# RFID_RC632.net
KiCad netlist of a schematic drawn in Altium Designer
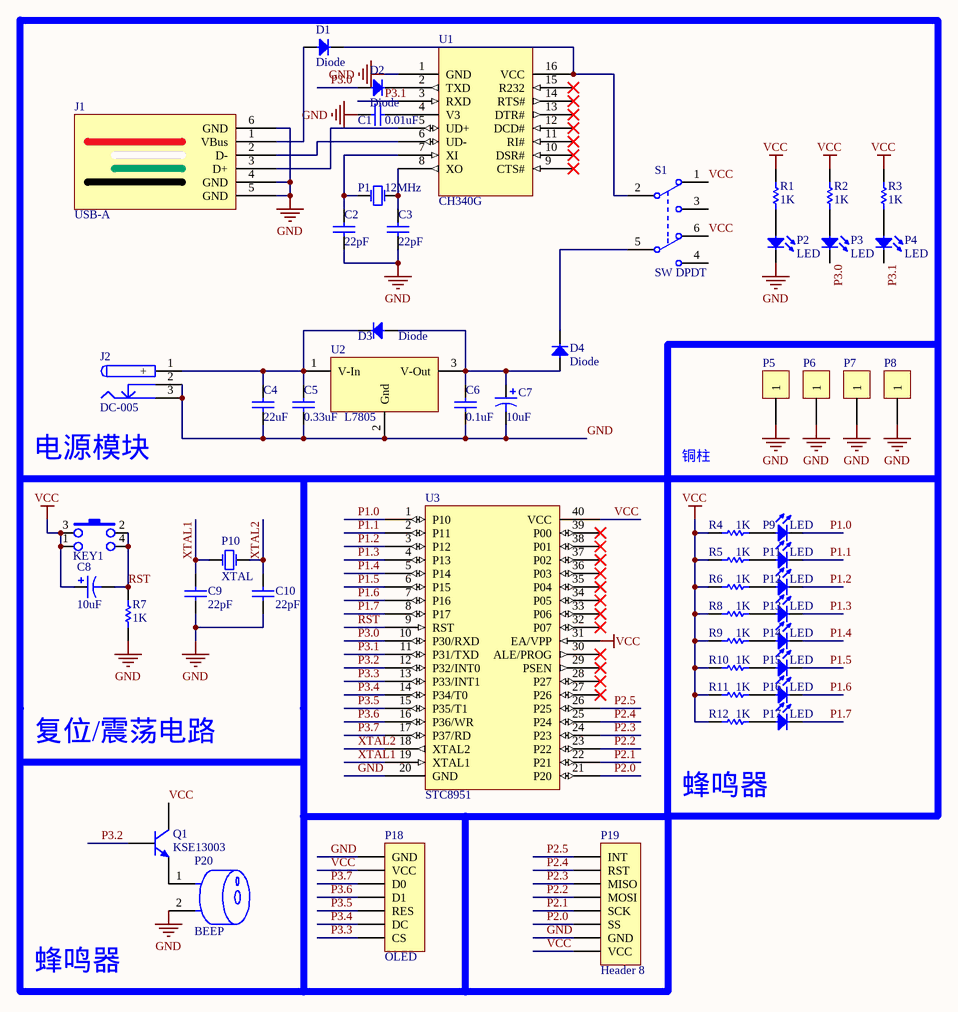
[diagram p0: RFID_RC632.SchDoc]

(export (version "E")
  (design (tool "Eeschema 10.0.6"))
  (components
    (comp (ref "C1")
      (value "0.01uF")
      (footprint "普通电容")
      (description "普通电容")
      (libsource (lib "RFID_RC632") (part "Cap"))
    )
    (comp (ref "C2")
      (value "22pF")
      (footprint "普通电容")
      (description "普通电容")
      (libsource (lib "RFID_RC632") (part "Cap"))
    )
    (comp (ref "C3")
      (value "22pF")
      (footprint "普通电容")
      (description "普通电容")
      (libsource (lib "RFID_RC632") (part "Cap"))
    )
    (comp (ref "C4")
      (value "22uF")
      (footprint "普通电容")
      (description "普通电容")
      (libsource (lib "RFID_RC632") (part "Cap"))
    )
    (comp (ref "C5")
      (value "0.33uF")
      (footprint "普通电容")
      (description "普通电容")
      (libsource (lib "RFID_RC632") (part "Cap"))
    )
    (comp (ref "C6")
      (value "0.1uF")
      (footprint "普通电容")
      (description "普通电容")
      (libsource (lib "RFID_RC632") (part "Cap"))
    )
    (comp (ref "C7")
      (value "10uF")
      (footprint "电解电容")
      (description "电解电容")
      (libsource (lib "RFID_RC632") (part "电解电容"))
    )
    (comp (ref "C8")
      (value "10uF")
      (footprint "电解电容")
      (description "电解电容")
      (libsource (lib "RFID_RC632") (part "电解电容"))
    )
    (comp (ref "C9")
      (value "22pF")
      (footprint "普通电容")
      (description "普通电容")
      (libsource (lib "RFID_RC632") (part "Cap"))
    )
    (comp (ref "C10")
      (value "22pF")
      (footprint "普通电容")
      (description "普通电容")
      (libsource (lib "RFID_RC632") (part "Cap"))
    )
    (comp (ref "D1")
      (value "Diode")
      (footprint "Diode")
      (description "二极管")
      (fields (field (name "PUBLISHER") "Altium Limited"))
      (libsource (lib "RFID_RC632") (part "Diode"))
    )
    (comp (ref "D2")
      (value "Diode")
      (footprint "Diode")
      (description "二极管")
      (fields (field (name "PUBLISHER") "Altium Limited"))
      (libsource (lib "RFID_RC632") (part "Diode"))
    )
    (comp (ref "D3")
      (value "Diode")
      (footprint "Diode")
      (description "二极管")
      (fields (field (name "PUBLISHER") "Altium Limited"))
      (libsource (lib "RFID_RC632") (part "Diode"))
    )
    (comp (ref "D4")
      (value "Diode")
      (footprint "Diode")
      (description "二极管")
      (fields (field (name "PUBLISHER") "Altium Limited"))
      (libsource (lib "RFID_RC632") (part "Diode"))
    )
    (comp (ref "J1") (value "USB-A") (footprint "USB-A") (libsource (lib "RFID_RC632") (part "USB-A")))
    (comp (ref "J2")
      (value "DC-005")
      (footprint "DC JACK")
      (description "DC 电源座")
      (fields (field (name "MANUFACTURER") "Kycon"))
      (libsource (lib "RFID_RC632") (part "DC JACK"))
    )
    (comp (ref "KEY1") (value "SW-66B7") (footprint "SW-66") (libsource (lib "RFID_RC632") (part "SW-66B7")))
    (comp (ref "P1") (value "12MHz") (footprint "晶振") (libsource (lib "RFID_RC632") (part "晶振")))
    (comp (ref "P2")
      (value "LED")
      (footprint "LED")
      (description "LED灯")
      (libsource (lib "RFID_RC632") (part "LED"))
    )
    (comp (ref "P3")
      (value "LED")
      (footprint "LED")
      (description "LED灯")
      (libsource (lib "RFID_RC632") (part "LED"))
    )
    (comp (ref "P4")
      (value "LED")
      (footprint "LED")
      (description "LED灯")
      (libsource (lib "RFID_RC632") (part "LED"))
    )
    (comp (ref "P5")
      (value "CU-M3X6-10")
      (footprint "CU-M3X6-10")
      (description "10mm长M3六角铜柱")
      (fields (field (name "PUBLISHER") "Altium Limited"))
      (libsource (lib "RFID_RC632") (part "CU-M3X6-10"))
    )
    (comp (ref "P6")
      (value "CU-M3X6-10")
      (footprint "CU-M3X6-10")
      (description "10mm长M3六角铜柱")
      (fields (field (name "PUBLISHER") "Altium Limited"))
      (libsource (lib "RFID_RC632") (part "CU-M3X6-10"))
    )
    (comp (ref "P7")
      (value "CU-M3X6-10")
      (footprint "CU-M3X6-10")
      (description "10mm长M3六角铜柱")
      (fields (field (name "PUBLISHER") "Altium Limited"))
      (libsource (lib "RFID_RC632") (part "CU-M3X6-10"))
    )
    (comp (ref "P8")
      (value "CU-M3X6-10")
      (footprint "CU-M3X6-10")
      (description "10mm长M3六角铜柱")
      (fields (field (name "PUBLISHER") "Altium Limited"))
      (libsource (lib "RFID_RC632") (part "CU-M3X6-10"))
    )
    (comp (ref "P9")
      (value "LED")
      (footprint "LED")
      (description "LED灯")
      (libsource (lib "RFID_RC632") (part "LED"))
    )
    (comp (ref "P10")
      (value "XTAL")
      (footprint "晶振")
      (description "晶振")
      (libsource (lib "RFID_RC632") (part "晶振"))
    )
    (comp (ref "P11")
      (value "LED")
      (footprint "LED")
      (description "LED灯")
      (libsource (lib "RFID_RC632") (part "LED"))
    )
    (comp (ref "P12")
      (value "LED")
      (footprint "LED")
      (description "LED灯")
      (libsource (lib "RFID_RC632") (part "LED"))
    )
    (comp (ref "P13")
      (value "LED")
      (footprint "LED")
      (description "LED灯")
      (libsource (lib "RFID_RC632") (part "LED"))
    )
    (comp (ref "P14")
      (value "LED")
      (footprint "LED")
      (description "LED灯")
      (libsource (lib "RFID_RC632") (part "LED"))
    )
    (comp (ref "P15")
      (value "LED")
      (footprint "LED")
      (description "LED灯")
      (libsource (lib "RFID_RC632") (part "LED"))
    )
    (comp (ref "P16")
      (value "LED")
      (footprint "LED")
      (description "LED灯")
      (libsource (lib "RFID_RC632") (part "LED"))
    )
    (comp (ref "P17")
      (value "LED")
      (footprint "LED")
      (description "LED灯")
      (libsource (lib "RFID_RC632") (part "LED"))
    )
    (comp (ref "P18")
      (value "OLED")
      (footprint "OLED")
      (description "OLED 0.96寸 SPI")
      (fields (field (name "PUBLISHER") "Altium Limited"))
      (libsource (lib "RFID_RC632") (part "OLED"))
    )
    (comp (ref "P19")
      (value "Header 8")
      (footprint "RFID")
      (description "Header, 8-Pin")
      (fields (field (name "PUBLISHER") "Altium Limited"))
      (libsource (lib "RFID_RC632") (part "RFID"))
    )
    (comp (ref "P20")
      (value "BEEP")
      (footprint "BEEP")
      (description "圆形蜂鸣器")
      (libsource (lib "RFID_RC632") (part "BEEP"))
    )
    (comp (ref "Q1")
      (value "KSE13003")
      (footprint "NPN KSE13003")
      (description "NPN 三极管")
      (fields (field (name "PUBLISHER") "Altium Limited"))
      (libsource (lib "RFID_RC632") (part "NPN KSE13003"))
    )
    (comp (ref "R1")
      (value "1K")
      (footprint "电阻")
      (description "电阻")
      (libsource (lib "RFID_RC632") (part "RES"))
    )
    (comp (ref "R2")
      (value "1K")
      (footprint "电阻")
      (description "电阻")
      (libsource (lib "RFID_RC632") (part "RES"))
    )
    (comp (ref "R3")
      (value "1K")
      (footprint "电阻")
      (description "电阻")
      (libsource (lib "RFID_RC632") (part "RES"))
    )
    (comp (ref "R4")
      (value "1K")
      (footprint "电阻")
      (description "电阻")
      (libsource (lib "RFID_RC632") (part "RES"))
    )
    (comp (ref "R5")
      (value "1K")
      (footprint "电阻")
      (description "电阻")
      (libsource (lib "RFID_RC632") (part "RES"))
    )
    (comp (ref "R6")
      (value "1K")
      (footprint "电阻")
      (description "电阻")
      (libsource (lib "RFID_RC632") (part "RES"))
    )
    (comp (ref "R7")
      (value "1K")
      (footprint "电阻")
      (description "电阻")
      (libsource (lib "RFID_RC632") (part "RES"))
    )
    (comp (ref "R8")
      (value "1K")
      (footprint "电阻")
      (description "电阻")
      (libsource (lib "RFID_RC632") (part "RES"))
    )
    (comp (ref "R9")
      (value "1K")
      (footprint "电阻")
      (description "电阻")
      (libsource (lib "RFID_RC632") (part "RES"))
    )
    (comp (ref "R10")
      (value "1K")
      (footprint "电阻")
      (description "电阻")
      (libsource (lib "RFID_RC632") (part "RES"))
    )
    (comp (ref "R11")
      (value "1K")
      (footprint "电阻")
      (description "电阻")
      (libsource (lib "RFID_RC632") (part "RES"))
    )
    (comp (ref "R12")
      (value "1K")
      (footprint "电阻")
      (description "电阻")
      (libsource (lib "RFID_RC632") (part "RES"))
    )
    (comp (ref "S1")
      (value "SW DPDT")
      (footprint "SW DPDT")
      (description "自锁开关 （双刀双掷）")
      (fields (field (name "PUBLISHER") "Altium Limited"))
      (libsource (lib "RFID_RC632") (part "SW DPDT"))
    )
    (comp (ref "U1")
      (value "CH340G")
      (footprint "CH340G")
      (description "USB to TTL Serial / UART")
      (libsource (lib "RFID_RC632") (part "CH340G"))
    )
    (comp (ref "U2")
      (value "L7805")
      (footprint "L7805")
      (description "1.5A Vin:40V(max) Vout:5-24V -55 ~ 150°C LDO稳压器")
      (libsource (lib "RFID_RC632") (part "L7805"))
    )
    (comp (ref "U3")
      (value "STC8951")
      (footprint "STC8951")
      (description "51单片机")
      (libsource (lib "RFID_RC632") (part "STC8951"))
    )
  )
  (nets
    (net (code "1") (name "/P1.0") (class "Default")
      (node (ref "P9") (pin "2") (pinfunction "K_2") (pintype "passive"))
      (node (ref "U3") (pin "1") (pinfunction "P10_1") (pintype "bidirectional"))
    )
    (net (code "2") (name "/P1.1") (class "Default")
      (node (ref "P11") (pin "2") (pinfunction "K_2") (pintype "passive"))
      (node (ref "U3") (pin "2") (pinfunction "P11_2") (pintype "bidirectional"))
    )
    (net (code "3") (name "/P1.2") (class "Default")
      (node (ref "P12") (pin "2") (pinfunction "K_2") (pintype "passive"))
      (node (ref "U3") (pin "3") (pinfunction "P12_3") (pintype "bidirectional"))
    )
    (net (code "4") (name "/P1.3") (class "Default")
      (node (ref "P13") (pin "2") (pinfunction "K_2") (pintype "passive"))
      (node (ref "U3") (pin "4") (pinfunction "P13_4") (pintype "bidirectional"))
    )
    (net (code "5") (name "/P1.4") (class "Default")
      (node (ref "P14") (pin "2") (pinfunction "K_2") (pintype "passive"))
      (node (ref "U3") (pin "5") (pinfunction "P14_5") (pintype "bidirectional"))
    )
    (net (code "6") (name "/P1.5") (class "Default")
      (node (ref "P15") (pin "2") (pinfunction "K_2") (pintype "passive"))
      (node (ref "U3") (pin "6") (pinfunction "P15_6") (pintype "bidirectional"))
    )
    (net (code "7") (name "/P1.6") (class "Default")
      (node (ref "P16") (pin "2") (pinfunction "K_2") (pintype "passive"))
      (node (ref "U3") (pin "7") (pinfunction "P16_7") (pintype "bidirectional"))
    )
    (net (code "8") (name "/P1.7") (class "Default")
      (node (ref "P17") (pin "2") (pinfunction "K_2") (pintype "passive"))
      (node (ref "U3") (pin "8") (pinfunction "P17_8") (pintype "bidirectional"))
    )
    (net (code "9") (name "/P2.0") (class "Default")
      (node (ref "P19") (pin "6") (pinfunction "SS_6") (pintype "passive"))
      (node (ref "U3") (pin "21") (pinfunction "P20_21") (pintype "bidirectional"))
    )
    (net (code "10") (name "/P2.1") (class "Default")
      (node (ref "P19") (pin "5") (pinfunction "SCK_5") (pintype "passive"))
      (node (ref "U3") (pin "22") (pinfunction "P21_22") (pintype "bidirectional"))
    )
    (net (code "11") (name "/P2.2") (class "Default")
      (node (ref "P19") (pin "4") (pinfunction "MOSI_4") (pintype "passive"))
      (node (ref "U3") (pin "23") (pinfunction "P22_23") (pintype "bidirectional"))
    )
    (net (code "12") (name "/P2.3") (class "Default")
      (node (ref "P19") (pin "3") (pinfunction "MISO_3") (pintype "passive"))
      (node (ref "U3") (pin "24") (pinfunction "P23_24") (pintype "bidirectional"))
    )
    (net (code "13") (name "/P2.4") (class "Default")
      (node (ref "P19") (pin "2") (pinfunction "RST_2") (pintype "passive"))
      (node (ref "U3") (pin "25") (pinfunction "P24_25") (pintype "bidirectional"))
    )
    (net (code "14") (name "/P2.5") (class "Default")
      (node (ref "P19") (pin "1") (pinfunction "INT_1") (pintype "passive"))
      (node (ref "U3") (pin "26") (pinfunction "P25_26") (pintype "bidirectional"))
    )
    (net (code "15") (name "/P3.0") (class "Default")
      (node (ref "D2") (pin "1") (pinfunction "A_1") (pintype "passive"))
      (node (ref "P3") (pin "2") (pinfunction "K_2") (pintype "passive"))
      (node (ref "U3") (pin "10") (pinfunction "P30/RXD_10") (pintype "bidirectional"))
    )
    (net (code "16") (name "/P3.1") (class "Default")
      (node (ref "P4") (pin "2") (pinfunction "K_2") (pintype "passive"))
      (node (ref "U1") (pin "3") (pinfunction "RXD_3") (pintype "input"))
      (node (ref "U3") (pin "11") (pinfunction "P31/TXD_11") (pintype "bidirectional"))
    )
    (net (code "17") (name "/P3.2") (class "Default")
      (node (ref "Q1") (pin "3") (pinfunction "B_3") (pintype "passive"))
      (node (ref "U3") (pin "12") (pinfunction "P32/INT0_12") (pintype "bidirectional"))
    )
    (net (code "18") (name "/P3.3") (class "Default")
      (node (ref "P18") (pin "7") (pinfunction "CS_7") (pintype "passive"))
      (node (ref "U3") (pin "13") (pinfunction "P33/INT1_13") (pintype "bidirectional"))
    )
    (net (code "19") (name "/P3.4") (class "Default")
      (node (ref "P18") (pin "6") (pinfunction "DC_6") (pintype "passive"))
      (node (ref "U3") (pin "14") (pinfunction "P34/T0_14") (pintype "bidirectional"))
    )
    (net (code "20") (name "/P3.5") (class "Default")
      (node (ref "P18") (pin "5") (pinfunction "RES_5") (pintype "passive"))
      (node (ref "U3") (pin "15") (pinfunction "P35/T1_15") (pintype "bidirectional"))
    )
    (net (code "21") (name "/P3.6") (class "Default")
      (node (ref "P18") (pin "4") (pinfunction "D1_4") (pintype "passive"))
      (node (ref "U3") (pin "16") (pinfunction "P36/WR_16") (pintype "bidirectional"))
    )
    (net (code "22") (name "/P3.7") (class "Default")
      (node (ref "P18") (pin "3") (pinfunction "D0_3") (pintype "passive"))
      (node (ref "U3") (pin "17") (pinfunction "P37/RD_17") (pintype "bidirectional"))
    )
    (net (code "23") (name "/RST") (class "Default")
      (node (ref "C8") (pin "2") (pinfunction "2_2") (pintype "passive"))
      (node (ref "KEY1") (pin "2") (pinfunction "2_2") (pintype "passive"))
      (node (ref "KEY1") (pin "4") (pinfunction "4_4") (pintype "passive"))
      (node (ref "R7") (pin "2") (pinfunction "2_2") (pintype "passive"))
      (node (ref "U3") (pin "9") (pinfunction "RST_9") (pintype "input"))
    )
    (net (code "24") (name "/XTAL1") (class "Default")
      (node (ref "C9") (pin "2") (pinfunction "2_2") (pintype "passive"))
      (node (ref "P10") (pin "1") (pinfunction "OSC1_1") (pintype "passive"))
      (node (ref "U3") (pin "19") (pinfunction "XTAL1_19") (pintype "input"))
    )
    (net (code "25") (name "/XTAL2") (class "Default")
      (node (ref "C10") (pin "2") (pinfunction "2_2") (pintype "passive"))
      (node (ref "P10") (pin "2") (pinfunction "OSC2_2") (pintype "passive"))
      (node (ref "U3") (pin "18") (pinfunction "XTAL2_18") (pintype "output"))
    )
    (net (code "26") (name "GND") (class "Default")
      (node (ref "C1") (pin "1") (pinfunction "1_1") (pintype "passive"))
      (node (ref "C10") (pin "1") (pinfunction "1_1") (pintype "passive"))
      (node (ref "C2") (pin "1") (pinfunction "1_1") (pintype "passive"))
      (node (ref "C3") (pin "1") (pinfunction "1_1") (pintype "passive"))
      (node (ref "C4") (pin "1") (pinfunction "1_1") (pintype "passive"))
      (node (ref "C5") (pin "1") (pinfunction "1_1") (pintype "passive"))
      (node (ref "C6") (pin "1") (pinfunction "1_1") (pintype "passive"))
      (node (ref "C7") (pin "2") (pinfunction "2_2") (pintype "passive"))
      (node (ref "C9") (pin "1") (pinfunction "1_1") (pintype "passive"))
      (node (ref "J1") (pin "4") (pinfunction "GND_4") (pintype "passive"))
      (node (ref "J1") (pin "5") (pinfunction "GND_5") (pintype "passive"))
      (node (ref "J1") (pin "6") (pinfunction "GND_6") (pintype "passive"))
      (node (ref "J2") (pin "2") (pintype "power_in"))
      (node (ref "J2") (pin "3") (pinfunction "-_3") (pintype "power_in"))
      (node (ref "P18") (pin "1") (pinfunction "GND_1") (pintype "passive"))
      (node (ref "P19") (pin "7") (pinfunction "GND_7") (pintype "passive"))
      (node (ref "P2") (pin "2") (pinfunction "K_2") (pintype "passive"))
      (node (ref "P20") (pin "2") (pinfunction "-_2") (pintype "passive"))
      (node (ref "P5") (pin "1") (pinfunction "1_1") (pintype "passive"))
      (node (ref "P6") (pin "1") (pinfunction "1_1") (pintype "passive"))
      (node (ref "P7") (pin "1") (pinfunction "1_1") (pintype "passive"))
      (node (ref "P8") (pin "1") (pinfunction "1_1") (pintype "passive"))
      (node (ref "R7") (pin "1") (pinfunction "1_1") (pintype "passive"))
      (node (ref "U1") (pin "1") (pinfunction "GND_1") (pintype "power_in"))
      (node (ref "U2") (pin "2") (pinfunction "Gnd_2") (pintype "passive"))
      (node (ref "U3") (pin "20") (pinfunction "GND_20") (pintype "power_in"))
    )
    (net (code "27") (name "Net-(D1-A)") (class "Default")
      (node (ref "D1") (pin "1") (pinfunction "A_1") (pintype "passive"))
      (node (ref "J1") (pin "1") (pinfunction "VBus_1") (pintype "passive"))
    )
    (net (code "28") (name "Net-(D1-K)") (class "Default")
      (node (ref "D1") (pin "2") (pinfunction "K_2") (pintype "passive"))
      (node (ref "S1") (pin "2") (pinfunction "COMMON1_2") (pintype "passive"))
      (node (ref "U1") (pin "16") (pinfunction "VCC_16") (pintype "power_in"))
    )
    (net (code "29") (name "Net-(D2-K)") (class "Default")
      (node (ref "D2") (pin "2") (pinfunction "K_2") (pintype "passive"))
      (node (ref "U1") (pin "2") (pinfunction "TXD_2") (pintype "output"))
    )
    (net (code "30") (name "Net-(D3-A)") (class "Default")
      (node (ref "C6") (pin "2") (pinfunction "2_2") (pintype "passive"))
      (node (ref "C7") (pin "1") (pinfunction "1_1") (pintype "passive"))
      (node (ref "D3") (pin "1") (pinfunction "A_1") (pintype "passive"))
      (node (ref "D4") (pin "1") (pinfunction "A_1") (pintype "passive"))
      (node (ref "U2") (pin "3") (pinfunction "V-Out_3") (pintype "passive"))
    )
    (net (code "31") (name "Net-(D3-K)") (class "Default")
      (node (ref "C4") (pin "2") (pinfunction "2_2") (pintype "passive"))
      (node (ref "C5") (pin "2") (pinfunction "2_2") (pintype "passive"))
      (node (ref "D3") (pin "2") (pinfunction "K_2") (pintype "passive"))
      (node (ref "J2") (pin "1") (pinfunction "+_1") (pintype "power_in"))
      (node (ref "U2") (pin "1") (pinfunction "V-In_1") (pintype "passive"))
    )
    (net (code "32") (name "Net-(D4-K)") (class "Default")
      (node (ref "D4") (pin "2") (pinfunction "K_2") (pintype "passive"))
      (node (ref "S1") (pin "5") (pinfunction "COMMON2_5") (pintype "passive"))
    )
    (net (code "33") (name "Net-(J1-D+)") (class "Default")
      (node (ref "J1") (pin "3") (pinfunction "D+_3") (pintype "passive"))
      (node (ref "U1") (pin "5") (pinfunction "UD+_5") (pintype "bidirectional"))
    )
    (net (code "34") (name "Net-(J1-D-)") (class "Default")
      (node (ref "J1") (pin "2") (pinfunction "D-_2") (pintype "passive"))
      (node (ref "U1") (pin "6") (pinfunction "UD-_6") (pintype "bidirectional"))
    )
    (net (code "35") (name "Net-(P1-OSC1)") (class "Default")
      (node (ref "C3") (pin "2") (pinfunction "2_2") (pintype "passive"))
      (node (ref "P1") (pin "1") (pinfunction "OSC1_1") (pintype "passive"))
      (node (ref "U1") (pin "8") (pinfunction "XO_8") (pintype "output"))
    )
    (net (code "36") (name "Net-(P1-OSC2)") (class "Default")
      (node (ref "C2") (pin "2") (pinfunction "2_2") (pintype "passive"))
      (node (ref "P1") (pin "2") (pinfunction "OSC2_2") (pintype "passive"))
      (node (ref "U1") (pin "7") (pinfunction "XI_7") (pintype "input"))
    )
    (net (code "37") (name "Net-(P2-A)") (class "Default")
      (node (ref "P2") (pin "1") (pinfunction "A_1") (pintype "passive"))
      (node (ref "R1") (pin "1") (pinfunction "1_1") (pintype "passive"))
    )
    (net (code "38") (name "Net-(P3-A)") (class "Default")
      (node (ref "P3") (pin "1") (pinfunction "A_1") (pintype "passive"))
      (node (ref "R2") (pin "1") (pinfunction "1_1") (pintype "passive"))
    )
    (net (code "39") (name "Net-(P4-A)") (class "Default")
      (node (ref "P4") (pin "1") (pinfunction "A_1") (pintype "passive"))
      (node (ref "R3") (pin "1") (pinfunction "1_1") (pintype "passive"))
    )
    (net (code "40") (name "Net-(P9-A)") (class "Default")
      (node (ref "P9") (pin "1") (pinfunction "A_1") (pintype "passive"))
      (node (ref "R4") (pin "2") (pinfunction "2_2") (pintype "passive"))
    )
    (net (code "41") (name "Net-(P11-A)") (class "Default")
      (node (ref "P11") (pin "1") (pinfunction "A_1") (pintype "passive"))
      (node (ref "R5") (pin "2") (pinfunction "2_2") (pintype "passive"))
    )
    (net (code "42") (name "Net-(P12-A)") (class "Default")
      (node (ref "P12") (pin "1") (pinfunction "A_1") (pintype "passive"))
      (node (ref "R6") (pin "2") (pinfunction "2_2") (pintype "passive"))
    )
    (net (code "43") (name "Net-(P13-A)") (class "Default")
      (node (ref "P13") (pin "1") (pinfunction "A_1") (pintype "passive"))
      (node (ref "R8") (pin "2") (pinfunction "2_2") (pintype "passive"))
    )
    (net (code "44") (name "Net-(P14-A)") (class "Default")
      (node (ref "P14") (pin "1") (pinfunction "A_1") (pintype "passive"))
      (node (ref "R9") (pin "2") (pinfunction "2_2") (pintype "passive"))
    )
    (net (code "45") (name "Net-(P15-A)") (class "Default")
      (node (ref "P15") (pin "1") (pinfunction "A_1") (pintype "passive"))
      (node (ref "R10") (pin "2") (pinfunction "2_2") (pintype "passive"))
    )
    (net (code "46") (name "Net-(P16-A)") (class "Default")
      (node (ref "P16") (pin "1") (pinfunction "A_1") (pintype "passive"))
      (node (ref "R11") (pin "2") (pinfunction "2_2") (pintype "passive"))
    )
    (net (code "47") (name "Net-(P17-A)") (class "Default")
      (node (ref "P17") (pin "1") (pinfunction "A_1") (pintype "passive"))
      (node (ref "R12") (pin "2") (pinfunction "2_2") (pintype "passive"))
    )
    (net (code "48") (name "Net-(P20-+)") (class "Default")
      (node (ref "P20") (pin "1") (pinfunction "+_1") (pintype "passive"))
      (node (ref "Q1") (pin "1") (pinfunction "E_1") (pintype "passive"))
    )
    (net (code "49") (name "Net-(U1-V3)") (class "Default")
      (node (ref "C1") (pin "2") (pinfunction "2_2") (pintype "passive"))
      (node (ref "U1") (pin "4") (pinfunction "V3_4") (pintype "power_in"))
    )
    (net (code "50") (name "VCC") (class "Default")
      (node (ref "C8") (pin "1") (pinfunction "1_1") (pintype "passive"))
      (node (ref "KEY1") (pin "1") (pinfunction "1_1") (pintype "passive"))
      (node (ref "KEY1") (pin "3") (pinfunction "3_3") (pintype "passive"))
      (node (ref "P18") (pin "2") (pinfunction "VCC_2") (pintype "passive"))
      (node (ref "P19") (pin "8") (pinfunction "VCC_8") (pintype "passive"))
      (node (ref "Q1") (pin "2") (pinfunction "C_2") (pintype "passive"))
      (node (ref "R1") (pin "2") (pinfunction "2_2") (pintype "passive"))
      (node (ref "R10") (pin "1") (pinfunction "1_1") (pintype "passive"))
      (node (ref "R11") (pin "1") (pinfunction "1_1") (pintype "passive"))
      (node (ref "R12") (pin "1") (pinfunction "1_1") (pintype "passive"))
      (node (ref "R2") (pin "2") (pinfunction "2_2") (pintype "passive"))
      (node (ref "R3") (pin "2") (pinfunction "2_2") (pintype "passive"))
      (node (ref "R4") (pin "1") (pinfunction "1_1") (pintype "passive"))
      (node (ref "R5") (pin "1") (pinfunction "1_1") (pintype "passive"))
      (node (ref "R6") (pin "1") (pinfunction "1_1") (pintype "passive"))
      (node (ref "R8") (pin "1") (pinfunction "1_1") (pintype "passive"))
      (node (ref "R9") (pin "1") (pinfunction "1_1") (pintype "passive"))
      (node (ref "S1") (pin "1") (pinfunction "NC1_1") (pintype "passive"))
      (node (ref "S1") (pin "6") (pinfunction "NC2_6") (pintype "passive"))
      (node (ref "U3") (pin "31") (pinfunction "EA/VPP_31") (pintype "input"))
      (node (ref "U3") (pin "40") (pinfunction "VCC_40") (pintype "power_in"))
    )
    (net (code "51") (name "unconnected-(S1-NO1-Pad3)") (class "Default")
      (node (ref "S1") (pin "3") (pinfunction "NO1_3") (pintype "passive"))
    )
    (net (code "52") (name "unconnected-(S1-NO2-Pad4)") (class "Default")
      (node (ref "S1") (pin "4") (pinfunction "NO2_4") (pintype "passive"))
    )
    (net (code "53") (name "unconnected-(U1-CTS#-Pad9)") (class "Default")
      (node (ref "U1") (pin "9") (pinfunction "CTS#_9") (pintype "input+no_connect"))
    )
    (net (code "54") (name "unconnected-(U1-DCD#-Pad12)") (class "Default")
      (node (ref "U1") (pin "12") (pinfunction "DCD#_12") (pintype "input+no_connect"))
    )
    (net (code "55") (name "unconnected-(U1-DSR#-Pad10)") (class "Default")
      (node (ref "U1") (pin "10") (pinfunction "DSR#_10") (pintype "input+no_connect"))
    )
    (net (code "56") (name "unconnected-(U1-DTR#-Pad13)") (class "Default")
      (node (ref "U1") (pin "13") (pinfunction "DTR#_13") (pintype "output+no_connect"))
    )
    (net (code "57") (name "unconnected-(U1-R232-Pad15)") (class "Default")
      (node (ref "U1") (pin "15") (pinfunction "R232_15") (pintype "input+no_connect"))
    )
    (net (code "58") (name "unconnected-(U1-RI#-Pad11)") (class "Default")
      (node (ref "U1") (pin "11") (pinfunction "RI#_11") (pintype "input+no_connect"))
    )
    (net (code "59") (name "unconnected-(U1-RTS#-Pad14)") (class "Default")
      (node (ref "U1") (pin "14") (pinfunction "RTS#_14") (pintype "output+no_connect"))
    )
    (net (code "60") (name "unconnected-(U3-ALE{slash}PROG-Pad30)") (class "Default")
      (node (ref "U3") (pin "30") (pinfunction "ALE/PROG_30") (pintype "output+no_connect"))
    )
    (net (code "61") (name "unconnected-(U3-P00-Pad39)") (class "Default")
      (node (ref "U3") (pin "39") (pinfunction "P00_39") (pintype "bidirectional+no_connect"))
    )
    (net (code "62") (name "unconnected-(U3-P01-Pad38)") (class "Default")
      (node (ref "U3") (pin "38") (pinfunction "P01_38") (pintype "bidirectional+no_connect"))
    )
    (net (code "63") (name "unconnected-(U3-P02-Pad37)") (class "Default")
      (node (ref "U3") (pin "37") (pinfunction "P02_37") (pintype "bidirectional+no_connect"))
    )
    (net (code "64") (name "unconnected-(U3-P03-Pad36)") (class "Default")
      (node (ref "U3") (pin "36") (pinfunction "P03_36") (pintype "bidirectional+no_connect"))
    )
    (net (code "65") (name "unconnected-(U3-P04-Pad35)") (class "Default")
      (node (ref "U3") (pin "35") (pinfunction "P04_35") (pintype "bidirectional+no_connect"))
    )
    (net (code "66") (name "unconnected-(U3-P05-Pad34)") (class "Default")
      (node (ref "U3") (pin "34") (pinfunction "P05_34") (pintype "bidirectional+no_connect"))
    )
    (net (code "67") (name "unconnected-(U3-P06-Pad33)") (class "Default")
      (node (ref "U3") (pin "33") (pinfunction "P06_33") (pintype "bidirectional+no_connect"))
    )
    (net (code "68") (name "unconnected-(U3-P07-Pad32)") (class "Default")
      (node (ref "U3") (pin "32") (pinfunction "P07_32") (pintype "bidirectional+no_connect"))
    )
    (net (code "69") (name "unconnected-(U3-P26-Pad27)") (class "Default")
      (node (ref "U3") (pin "27") (pinfunction "P26_27") (pintype "bidirectional+no_connect"))
    )
    (net (code "70") (name "unconnected-(U3-P27-Pad28)") (class "Default")
      (node (ref "U3") (pin "28") (pinfunction "P27_28") (pintype "bidirectional+no_connect"))
    )
    (net (code "71") (name "unconnected-(U3-PSEN-Pad29)") (class "Default")
      (node (ref "U3") (pin "29") (pinfunction "PSEN_29") (pintype "output+no_connect"))
    )
  )
)
